# SCH_Johan_s-project_2025-10-18.net
KiCad netlist of a schematic drawn in EasyEDA
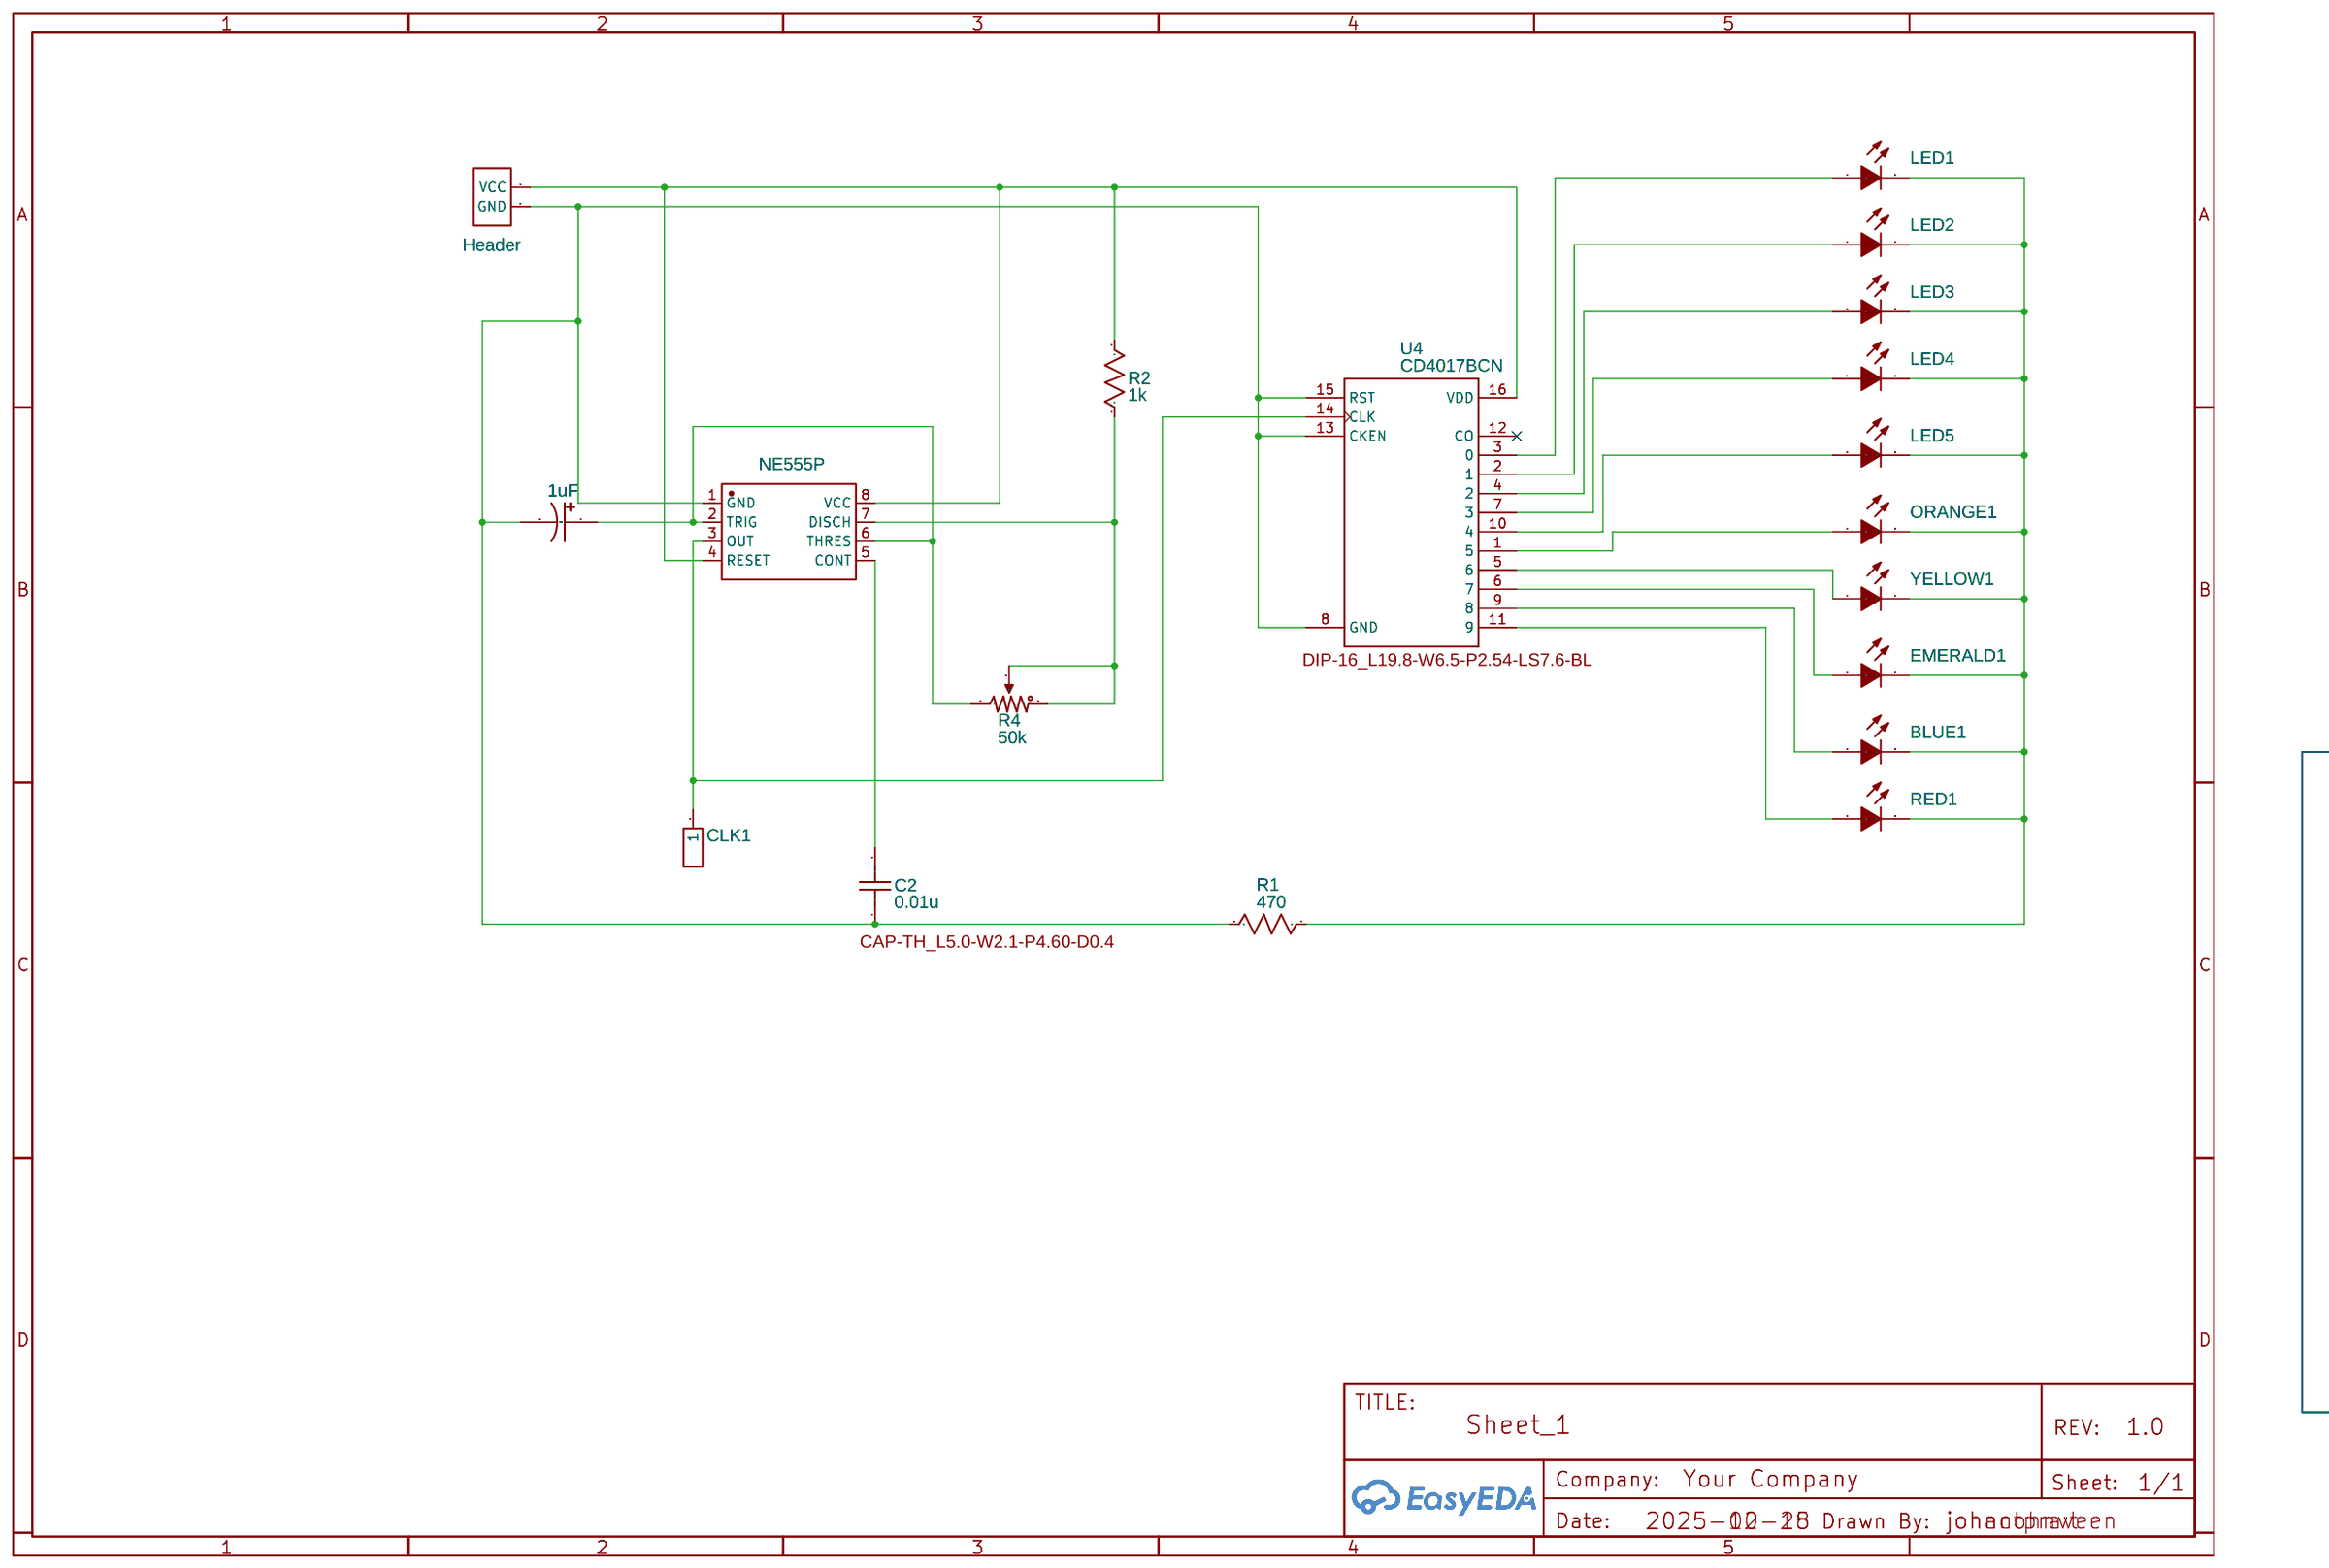
[diagram p0: schematic sheet]

(export (version "E")
  (design (tool "Eeschema 10.0.6"))
  (components
    (comp (ref "BLUE1") (value "LED_5MM") (libsource (lib "") (part "LED_5MM")))
    (comp (ref "C1")
      (value "1uF")
      (fields (field (name "Manufacturer Part") "UVZ1H010MDD") (field (name "Manufacturer") "Nichicon(尼吉康)"))
      (libsource (lib "") (part "UVZ1H010MDD"))
    )
    (comp (ref "C2") (value "0.01u") (libsource (lib "") (part "C_0603_US")))
    (comp (ref "CLK1")
      (value "C81276")
      (fields
        (field (name "Manufacturer Part") "2.54-1*1P针")
        (field (name "Manufacturer") "BOOMELE(Boom Precision Elec)")
      )
      (libsource (lib "") (part "Header-Male-2.54_1x1"))
    )
    (comp (ref "EMERALD1") (value "LED_5MM") (libsource (lib "") (part "LED_5MM_1")))
    (comp (ref "H1") (value "Header") (libsource (lib "") (part "HEADER-FEMALE-2.54_1X2")))
    (comp (ref "LED1") (value "LED_5MM") (libsource (lib "") (part "LED_5MM_2")))
    (comp (ref "LED2") (value "LED_5MM") (libsource (lib "") (part "LED_5MM_2")))
    (comp (ref "LED3") (value "LED_5MM") (libsource (lib "") (part "LED_5MM_2")))
    (comp (ref "LED4") (value "LED_5MM") (libsource (lib "") (part "LED_5MM_2")))
    (comp (ref "LED5") (value "LED_5MM") (libsource (lib "") (part "LED_5MM_2")))
    (comp (ref "ORANGE1") (value "LED_5MM") (libsource (lib "") (part "LED_5MM_5")))
    (comp (ref "R1")
      (value "470")
      (fields (field (name "Manufacturer Part") "?"))
      (libsource (lib "") (part "Resistor_1"))
    )
    (comp (ref "R2")
      (value "1k")
      (fields (field (name "Manufacturer Part") "?"))
      (libsource (lib "") (part "Resistor"))
    )
    (comp (ref "R4")
      (value "50k")
      (fields (field (name "Manufacturer Part") "?"))
      (libsource (lib "") (part "Potentiometer"))
    )
    (comp (ref "RED1") (value "LED_5MM") (libsource (lib "") (part "LED_5MM_4")))
    (comp (ref "U2")
      (value "NE555P")
      (fields (field (name "Manufacturer") "TI(德州仪器)"))
      (libsource (lib "") (part "NE555P"))
    )
    (comp (ref "U4") (value "CD4017BCN") (libsource (lib "") (part "CD4017BCN")))
    (comp (ref "YELLOW1") (value "LED_5MM") (libsource (lib "") (part "LED_5MM_3")))
  )
  (nets
    (net (code "1") (name "Net-(BLUE1-A)") (class "Default")
      (node (ref "BLUE1") (pin "1") (pinfunction "A_1") (pintype "input"))
      (node (ref "U4") (pin "9") (pinfunction "8_9") (pintype "output"))
    )
    (net (code "2") (name "Net-(BLUE1-K)") (class "Default")
      (node (ref "BLUE1") (pin "2") (pinfunction "K_2") (pintype "input"))
      (node (ref "EMERALD1") (pin "2") (pinfunction "K_2") (pintype "input"))
      (node (ref "LED1") (pin "2") (pinfunction "K_2") (pintype "input"))
      (node (ref "LED2") (pin "2") (pinfunction "K_2") (pintype "input"))
      (node (ref "LED3") (pin "2") (pinfunction "K_2") (pintype "input"))
      (node (ref "LED4") (pin "2") (pinfunction "K_2") (pintype "input"))
      (node (ref "LED5") (pin "2") (pinfunction "K_2") (pintype "input"))
      (node (ref "ORANGE1") (pin "2") (pinfunction "K_2") (pintype "input"))
      (node (ref "R1") (pin "1") (pinfunction "1_1") (pintype "unspecified"))
      (node (ref "RED1") (pin "2") (pinfunction "K_2") (pintype "input"))
      (node (ref "YELLOW1") (pin "2") (pinfunction "K_2") (pintype "input"))
    )
    (net (code "3") (name "Net-(EMERALD1-A)") (class "Default")
      (node (ref "EMERALD1") (pin "1") (pinfunction "A_1") (pintype "input"))
      (node (ref "U4") (pin "6") (pinfunction "7_6") (pintype "output"))
    )
    (net (code "4") (name "Net-(H1-GND)") (class "Default")
      (node (ref "C1") (pin "2") (pinfunction "2_2") (pintype "unspecified"))
      (node (ref "C2") (pin "1") (pinfunction "1_1") (pintype "unspecified"))
      (node (ref "H1") (pin "2") (pinfunction "GND_2") (pintype "unspecified"))
      (node (ref "R1") (pin "2") (pinfunction "2_2") (pintype "unspecified"))
      (node (ref "U2") (pin "1") (pinfunction "GND_1") (pintype "unspecified"))
      (node (ref "U4") (pin "13") (pinfunction "CKEN_13") (pintype "unspecified"))
      (node (ref "U4") (pin "15") (pinfunction "RST_15") (pintype "unspecified"))
      (node (ref "U4") (pin "8") (pinfunction "GND_8") (pintype "passive"))
    )
    (net (code "5") (name "Net-(H1-VCC)") (class "Default")
      (node (ref "H1") (pin "1") (pinfunction "VCC_1") (pintype "unspecified"))
      (node (ref "R2") (pin "1") (pinfunction "1_1") (pintype "unspecified"))
      (node (ref "U2") (pin "4") (pinfunction "RESET_4") (pintype "unspecified"))
      (node (ref "U2") (pin "8") (pinfunction "VCC_8") (pintype "unspecified"))
      (node (ref "U4") (pin "16") (pinfunction "VDD_16") (pintype "passive"))
    )
    (net (code "6") (name "Net-(LED1-A)") (class "Default")
      (node (ref "LED1") (pin "1") (pinfunction "A_1") (pintype "input"))
      (node (ref "U4") (pin "3") (pinfunction "0_3") (pintype "output"))
    )
    (net (code "7") (name "Net-(LED2-A)") (class "Default")
      (node (ref "LED2") (pin "1") (pinfunction "A_1") (pintype "input"))
      (node (ref "U4") (pin "2") (pinfunction "1_2") (pintype "output"))
    )
    (net (code "8") (name "Net-(LED3-A)") (class "Default")
      (node (ref "LED3") (pin "1") (pinfunction "A_1") (pintype "input"))
      (node (ref "U4") (pin "4") (pinfunction "2_4") (pintype "output"))
    )
    (net (code "9") (name "Net-(LED4-A)") (class "Default")
      (node (ref "LED4") (pin "1") (pinfunction "A_1") (pintype "input"))
      (node (ref "U4") (pin "7") (pinfunction "3_7") (pintype "output"))
    )
    (net (code "10") (name "Net-(LED5-A)") (class "Default")
      (node (ref "LED5") (pin "1") (pinfunction "A_1") (pintype "input"))
      (node (ref "U4") (pin "10") (pinfunction "4_10") (pintype "output"))
    )
    (net (code "11") (name "Net-(ORANGE1-A)") (class "Default")
      (node (ref "ORANGE1") (pin "1") (pinfunction "A_1") (pintype "input"))
      (node (ref "U4") (pin "1") (pinfunction "5_1") (pintype "output"))
    )
    (net (code "12") (name "Net-(R4-2)") (class "Default")
      (node (ref "R2") (pin "2") (pinfunction "2_2") (pintype "unspecified"))
      (node (ref "R4") (pin "2") (pinfunction "3_2") (pintype "unspecified"))
      (node (ref "R4") (pin "3") (pinfunction "2_3") (pintype "unspecified"))
      (node (ref "U2") (pin "7") (pinfunction "DISCH_7") (pintype "unspecified"))
    )
    (net (code "13") (name "Net-(RED1-A)") (class "Default")
      (node (ref "RED1") (pin "1") (pinfunction "A_1") (pintype "input"))
      (node (ref "U4") (pin "11") (pinfunction "9_11") (pintype "output"))
    )
    (net (code "14") (name "Net-(U2-CONT)") (class "Default")
      (node (ref "C2") (pin "2") (pinfunction "2_2") (pintype "unspecified"))
      (node (ref "U2") (pin "5") (pinfunction "CONT_5") (pintype "unspecified"))
    )
    (net (code "15") (name "Net-(U2-OUT)") (class "Default")
      (node (ref "CLK1") (pin "1") (pinfunction "1_1") (pintype "unspecified"))
      (node (ref "U2") (pin "3") (pinfunction "OUT_3") (pintype "unspecified"))
      (node (ref "U4") (pin "14") (pinfunction "CLK_14") (pintype "unspecified"))
    )
    (net (code "16") (name "Net-(U2-THRES)") (class "Default")
      (node (ref "C1") (pin "1") (pinfunction "1_1") (pintype "unspecified"))
      (node (ref "R4") (pin "1") (pinfunction "1_1") (pintype "unspecified"))
      (node (ref "U2") (pin "2") (pinfunction "TRIG_2") (pintype "unspecified"))
      (node (ref "U2") (pin "6") (pinfunction "THRES_6") (pintype "unspecified"))
    )
    (net (code "17") (name "Net-(U4-6)") (class "Default")
      (node (ref "U4") (pin "5") (pinfunction "6_5") (pintype "output"))
      (node (ref "YELLOW1") (pin "1") (pinfunction "A_1") (pintype "input"))
    )
    (net (code "18") (name "unconnected-(U4-CO-Pad12)") (class "Default")
      (node (ref "U4") (pin "12") (pinfunction "CO_12") (pintype "output+no_connect"))
    )
  )
)
